# Soil_Temperature_Sensors.net
KiCad netlist of a schematic drawn in Altium Designer
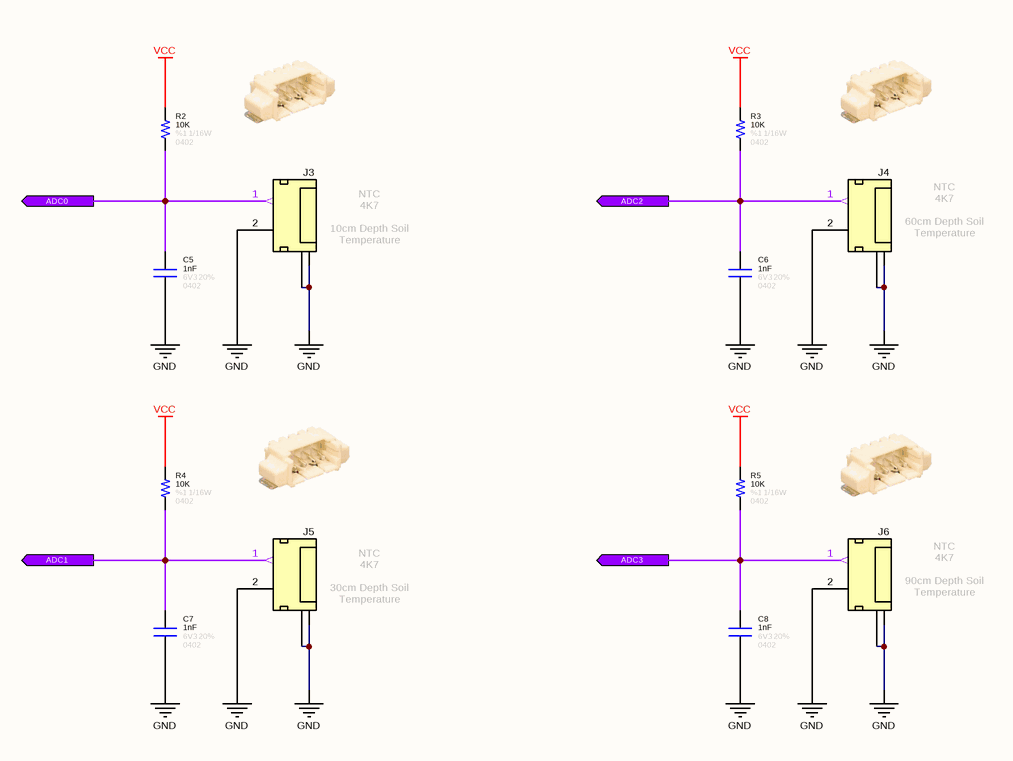
[diagram p0: Soil Temperature Sensors.SchDoc]

(export (version "E")
  (design (tool "Eeschema 10.0.6"))
  (components
    (comp (ref "C5")
      (value "1nF")
      (footprint "CAPACITOR_0402")
      (description "Capacitor - 1nF [0402] (Ceramic)")
      (fields
        (field (name "MANUFACTURER PART NUMBER") "04026C102MAT2A")
        (field (name "TOLERANCE") "20%")
        (field (name "CASE") "0402")
        (field (name "VOLTAGE") "6V3")
      )
      (libsource (lib "P101DA_Library") (part "Capacitor - 1nF [0402-6V3]"))
    )
    (comp (ref "C6")
      (value "1nF")
      (footprint "CAPACITOR_0402")
      (description "Capacitor - 1nF [0402] (Ceramic)")
      (fields
        (field (name "MANUFACTURER PART NUMBER") "04026C102MAT2A")
        (field (name "TOLERANCE") "20%")
        (field (name "CASE") "0402")
        (field (name "VOLTAGE") "6V3")
      )
      (libsource (lib "P101DA_Library") (part "Capacitor - 1nF [0402-6V3]"))
    )
    (comp (ref "C7")
      (value "1nF")
      (footprint "CAPACITOR_0402")
      (description "Capacitor - 1nF [0402] (Ceramic)")
      (fields
        (field (name "MANUFACTURER PART NUMBER") "04026C102MAT2A")
        (field (name "TOLERANCE") "20%")
        (field (name "CASE") "0402")
        (field (name "VOLTAGE") "6V3")
      )
      (libsource (lib "P101DA_Library") (part "Capacitor - 1nF [0402-6V3]"))
    )
    (comp (ref "C8")
      (value "1nF")
      (footprint "CAPACITOR_0402")
      (description "Capacitor - 1nF [0402] (Ceramic)")
      (fields
        (field (name "MANUFACTURER PART NUMBER") "04026C102MAT2A")
        (field (name "TOLERANCE") "20%")
        (field (name "CASE") "0402")
        (field (name "VOLTAGE") "6V3")
      )
      (libsource (lib "P101DA_Library") (part "Capacitor - 1nF [0402-6V3]"))
    )
    (comp (ref "J3")
      (value "2P SMD Tunic Connector")
      (footprint "Connector_Tunic 2P")
      (description "Mini Tunic Connector with 2P")
      (fields
        (field (name "MANUFACTURER PART NUMBER") "53261-0271")
        (field (name "MOUSER PART NUMBER") "538-53261-0271")
      )
      (libsource (lib "P101DA_Library") (part "Connector - Mini Tunic 2P (1.25)"))
    )
    (comp (ref "J4")
      (value "2P SMD Tunic Connector")
      (footprint "Connector_Tunic 2P")
      (description "Mini Tunic Connector with 2P")
      (fields
        (field (name "MANUFACTURER PART NUMBER") "53261-0271")
        (field (name "MOUSER PART NUMBER") "538-53261-0271")
      )
      (libsource (lib "P101DA_Library") (part "Connector - Mini Tunic 2P (1.25)"))
    )
    (comp (ref "J5")
      (value "2P SMD Tunic Connector")
      (footprint "Connector_Tunic 2P")
      (description "Mini Tunic Connector with 2P")
      (fields
        (field (name "MANUFACTURER PART NUMBER") "53261-0271")
        (field (name "MOUSER PART NUMBER") "538-53261-0271")
      )
      (libsource (lib "P101DA_Library") (part "Connector - Mini Tunic 2P (1.25)"))
    )
    (comp (ref "J6")
      (value "2P SMD Tunic Connector")
      (footprint "Connector_Tunic 2P")
      (description "Mini Tunic Connector with 2P")
      (fields
        (field (name "MANUFACTURER PART NUMBER") "53261-0271")
        (field (name "MOUSER PART NUMBER") "538-53261-0271")
      )
      (libsource (lib "P101DA_Library") (part "Connector - Mini Tunic 2P (1.25)"))
    )
    (comp (ref "R2")
      (value "10K")
      (footprint "RESISTOR_0402")
      (description "Thick Film Resistors - SMD 1/16 W 10 KOhm 1%")
      (fields
        (field (name "MANUFACTURER PART NUMBER") "CRCW040210K0FKED")
        (field (name "TOLERANCE") "%1")
        (field (name "CASE") "0402")
        (field (name "POWER") "1/16W")
        (field (name "Comment") "10K - 0402 - %1 - 1/16W")
      )
      (libsource (lib "P101DA_Library") (part "Resistor - 10K [0402]"))
    )
    (comp (ref "R3")
      (value "10K")
      (footprint "RESISTOR_0402")
      (description "Thick Film Resistors - SMD 1/16 W 10 KOhm 1%")
      (fields
        (field (name "MANUFACTURER PART NUMBER") "CRCW040210K0FKED")
        (field (name "TOLERANCE") "%1")
        (field (name "CASE") "0402")
        (field (name "POWER") "1/16W")
        (field (name "Comment") "10K - 0402 - %1 - 1/16W")
      )
      (libsource (lib "P101DA_Library") (part "Resistor - 10K [0402]"))
    )
    (comp (ref "R4")
      (value "10K")
      (footprint "RESISTOR_0402")
      (description "Thick Film Resistors - SMD 1/16 W 10 KOhm 1%")
      (fields
        (field (name "MANUFACTURER PART NUMBER") "CRCW040210K0FKED")
        (field (name "TOLERANCE") "%1")
        (field (name "CASE") "0402")
        (field (name "POWER") "1/16W")
        (field (name "Comment") "10K - 0402 - %1 - 1/16W")
      )
      (libsource (lib "P101DA_Library") (part "Resistor - 10K [0402]"))
    )
    (comp (ref "R5")
      (value "10K")
      (footprint "RESISTOR_0402")
      (description "Thick Film Resistors - SMD 1/16 W 10 KOhm 1%")
      (fields
        (field (name "MANUFACTURER PART NUMBER") "CRCW040210K0FKED")
        (field (name "TOLERANCE") "%1")
        (field (name "CASE") "0402")
        (field (name "POWER") "1/16W")
        (field (name "Comment") "10K - 0402 - %1 - 1/16W")
      )
      (libsource (lib "P101DA_Library") (part "Resistor - 10K [0402]"))
    )
  )
  (nets
    (net (code "1") (name "/ADC0") (class "Default")
      (node (ref "C5") (pin "2") (pinfunction "2_2") (pintype "passive"))
      (node (ref "J3") (pin "1") (pinfunction "Pin1_1") (pintype "output"))
      (node (ref "R2") (pin "1") (pinfunction "1_1") (pintype "passive"))
    )
    (net (code "2") (name "/ADC1") (class "Default")
      (node (ref "C7") (pin "2") (pinfunction "2_2") (pintype "passive"))
      (node (ref "J5") (pin "1") (pinfunction "Pin1_1") (pintype "output"))
      (node (ref "R4") (pin "1") (pinfunction "1_1") (pintype "passive"))
    )
    (net (code "3") (name "/ADC2") (class "Default")
      (node (ref "C6") (pin "2") (pinfunction "2_2") (pintype "passive"))
      (node (ref "J4") (pin "1") (pinfunction "Pin1_1") (pintype "output"))
      (node (ref "R3") (pin "1") (pinfunction "1_1") (pintype "passive"))
    )
    (net (code "4") (name "/ADC3") (class "Default")
      (node (ref "C8") (pin "2") (pinfunction "2_2") (pintype "passive"))
      (node (ref "J6") (pin "1") (pinfunction "Pin1_1") (pintype "output"))
      (node (ref "R5") (pin "1") (pinfunction "1_1") (pintype "passive"))
    )
    (net (code "5") (name "GND") (class "Default")
      (node (ref "C5") (pin "1") (pinfunction "1_1") (pintype "passive"))
      (node (ref "C6") (pin "1") (pinfunction "1_1") (pintype "passive"))
      (node (ref "C7") (pin "1") (pinfunction "1_1") (pintype "passive"))
      (node (ref "C8") (pin "1") (pinfunction "1_1") (pintype "passive"))
      (node (ref "J3") (pin "2") (pinfunction "Pin2_2") (pintype "passive"))
      (node (ref "J3") (pin "3") (pinfunction "GND_3") (pintype "passive"))
      (node (ref "J3") (pin "4") (pinfunction "GND_4") (pintype "passive"))
      (node (ref "J4") (pin "2") (pinfunction "Pin2_2") (pintype "passive"))
      (node (ref "J4") (pin "3") (pinfunction "GND_3") (pintype "passive"))
      (node (ref "J4") (pin "4") (pinfunction "GND_4") (pintype "passive"))
      (node (ref "J5") (pin "2") (pinfunction "Pin2_2") (pintype "passive"))
      (node (ref "J5") (pin "3") (pinfunction "GND_3") (pintype "passive"))
      (node (ref "J5") (pin "4") (pinfunction "GND_4") (pintype "passive"))
      (node (ref "J6") (pin "2") (pinfunction "Pin2_2") (pintype "passive"))
      (node (ref "J6") (pin "3") (pinfunction "GND_3") (pintype "passive"))
      (node (ref "J6") (pin "4") (pinfunction "GND_4") (pintype "passive"))
    )
    (net (code "6") (name "VCC") (class "Default")
      (node (ref "R2") (pin "2") (pinfunction "2_2") (pintype "passive"))
      (node (ref "R3") (pin "2") (pinfunction "2_2") (pintype "passive"))
      (node (ref "R4") (pin "2") (pinfunction "2_2") (pintype "passive"))
      (node (ref "R5") (pin "2") (pinfunction "2_2") (pintype "passive"))
    )
  )
)
